# untitled.net
KiCad netlist of a schematic drawn in EAGLE
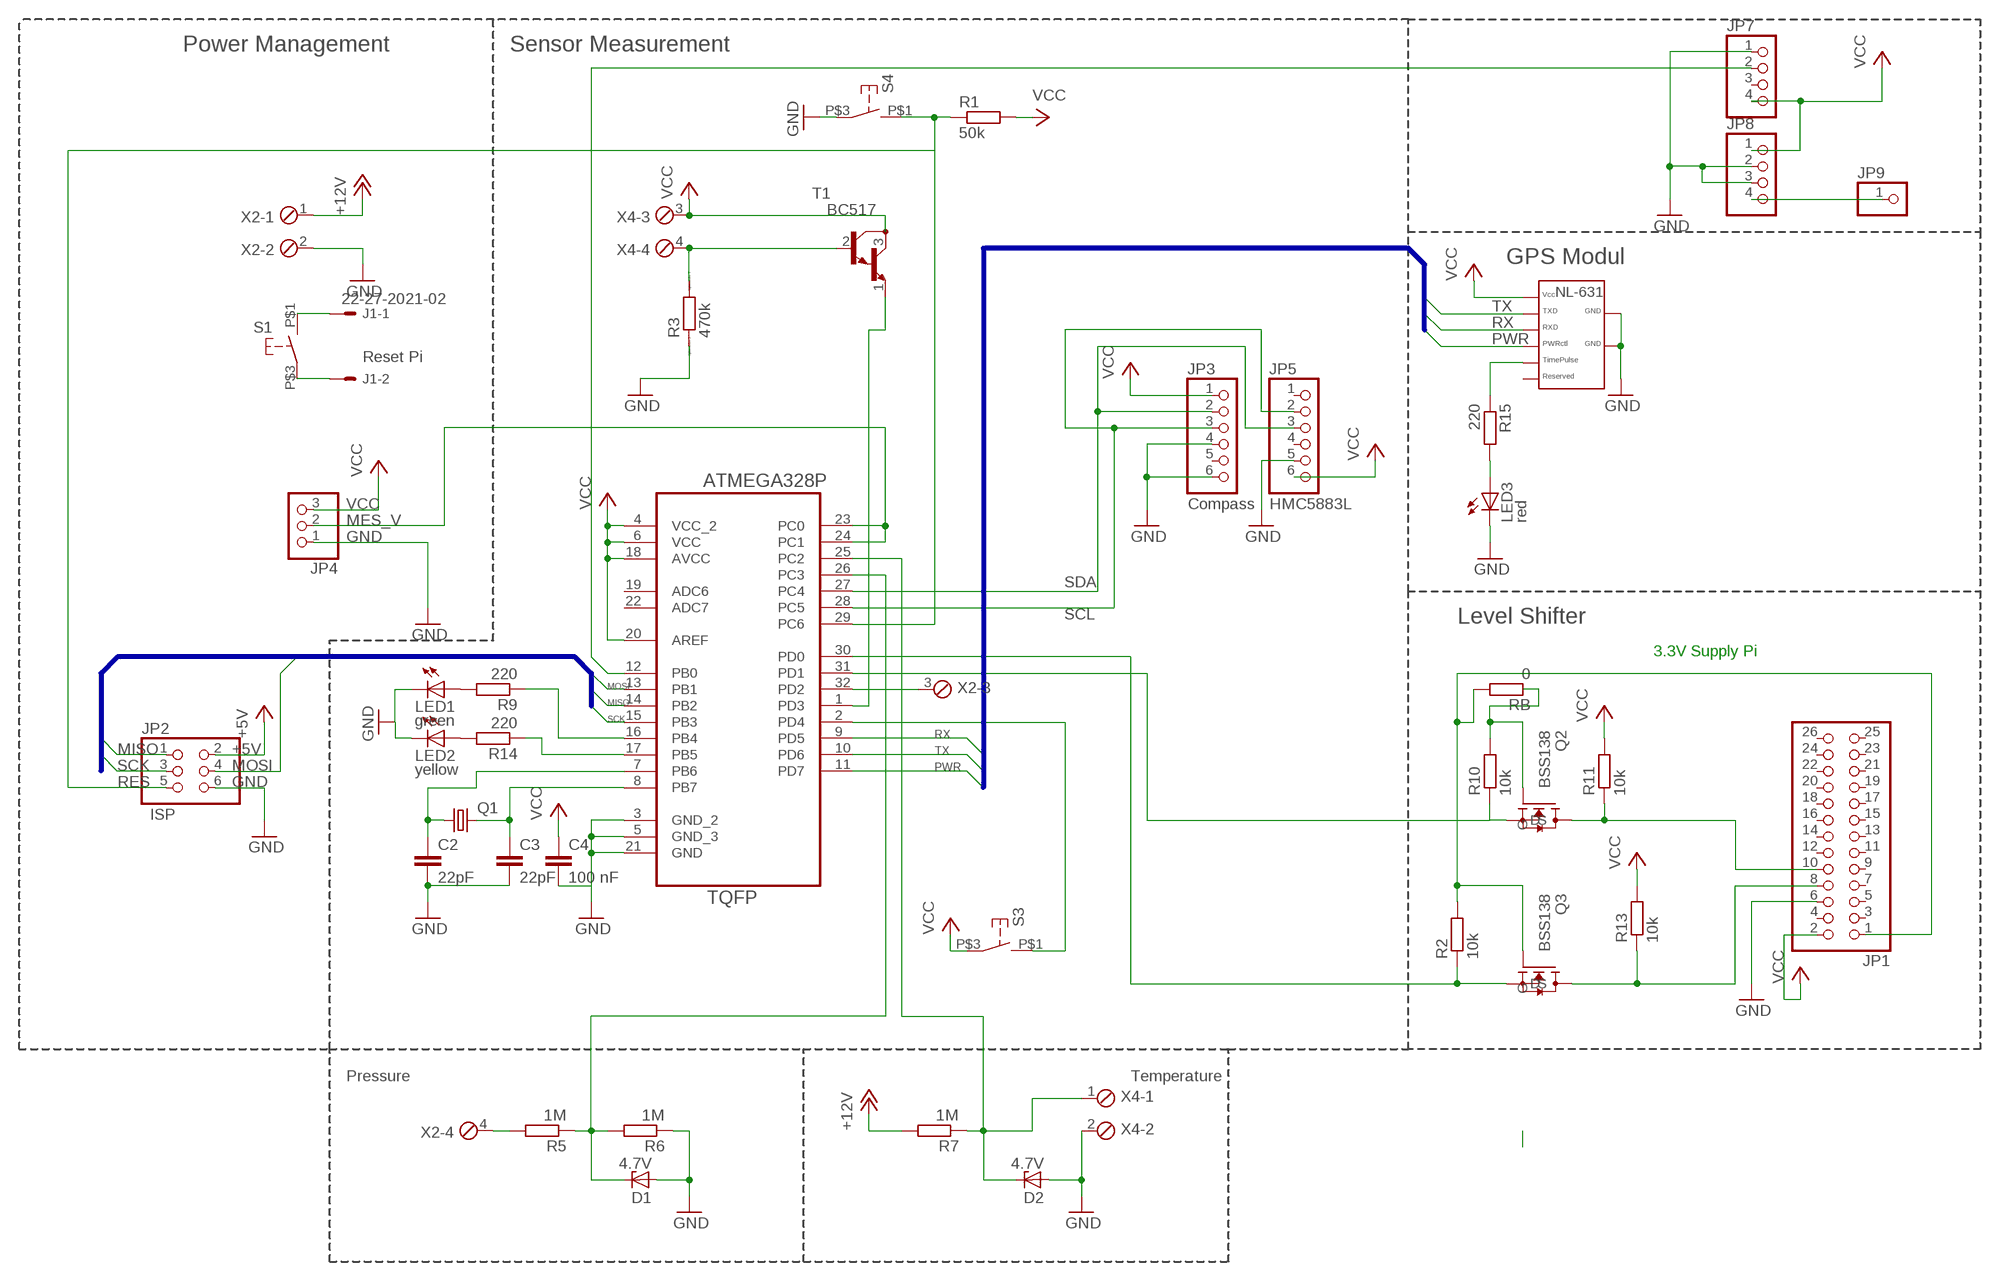
[diagram p0: schematic, sheet 1]

(export (version "E")
  (design (tool "Eeschema 10.0.6"))
  (components
    (comp (ref "C2")
      (value "22pF")
      (footprint "eagle-import:C1206")
      (libsource (lib "eagle-import") (part "C-EUC1206"))
    )
    (comp (ref "C3")
      (value "22pF")
      (footprint "eagle-import:C1206")
      (libsource (lib "eagle-import") (part "C-EUC1206"))
    )
    (comp (ref "C4")
      (value "100 nF")
      (footprint "eagle-import:C0603")
      (libsource (lib "eagle-import") (part "C-EUC0603"))
    )
    (comp (ref "D1")
      (value "4.7V")
      (footprint "eagle-import:SOT23")
      (libsource (lib "eagle-import") (part "ZENER-DIODESOT23"))
    )
    (comp (ref "D2")
      (value "4.7V")
      (footprint "eagle-import:SOT23")
      (libsource (lib "eagle-import") (part "ZENER-DIODESOT23"))
    )
    (comp (ref "IC1")
      (value "ATMEGA328P-AU")
      (footprint "eagle-import:QFP80P900X900X120-32N")
      (libsource (lib "eagle-import") (part "ATMEGA328P-AU"))
    )
    (comp (ref "J1")
      (value "22-27-2021-02")
      (footprint "eagle-import:6410-02")
      (libsource (lib "eagle-import") (part "22-?-0227-2021"))
    )
    (comp (ref "JP1")
      (value "PINHD-2X13")
      (footprint "eagle-import:2X13")
      (libsource (lib "eagle-import") (part "PINHD-2X13"))
    )
    (comp (ref "JP2")
      (value "PINHD-2X3")
      (footprint "eagle-import:2X03")
      (libsource (lib "eagle-import") (part "PINHD-2X3"))
    )
    (comp (ref "JP3")
      (value "Compass")
      (footprint "eagle-import:1X06")
      (libsource (lib "eagle-import") (part "PINHD-1X6"))
    )
    (comp (ref "JP4")
      (value "PINHD-1X3")
      (footprint "eagle-import:1X03")
      (libsource (lib "eagle-import") (part "PINHD-1X3"))
    )
    (comp (ref "JP5")
      (value "HMC5883L")
      (footprint "eagle-import:1X06")
      (libsource (lib "eagle-import") (part "PINHD-1X6"))
    )
    (comp (ref "JP7")
      (value "PINHD-1X4")
      (footprint "eagle-import:1X04")
      (libsource (lib "eagle-import") (part "PINHD-1X4"))
    )
    (comp (ref "JP8")
      (value "PINHD-1X4")
      (footprint "eagle-import:1X04")
      (libsource (lib "eagle-import") (part "PINHD-1X4"))
    )
    (comp (ref "JP9")
      (value "PINHD-1X1")
      (footprint "eagle-import:1X01")
      (libsource (lib "eagle-import") (part "PINHD-1X1"))
    )
    (comp (ref "LED1")
      (value "green")
      (footprint "eagle-import:LED3MM")
      (libsource (lib "eagle-import") (part "LED3MM"))
    )
    (comp (ref "LED2")
      (value "yellow")
      (footprint "eagle-import:LED3MM")
      (libsource (lib "eagle-import") (part "LED3MM"))
    )
    (comp (ref "LED3")
      (value "red")
      (footprint "eagle-import:LED3MM")
      (libsource (lib "eagle-import") (part "LED3MM"))
    )
    (comp (ref "Q1")
      (value "CRYSTALHC49UP")
      (footprint "eagle-import:HC49UP")
      (libsource (lib "eagle-import") (part "CRYSTALHC49UP"))
    )
    (comp (ref "Q2")
      (value "BSS138")
      (footprint "eagle-import:BSS138")
      (libsource (lib "eagle-import") (part "BSS138"))
    )
    (comp (ref "Q3")
      (value "BSS138")
      (footprint "eagle-import:BSS138")
      (libsource (lib "eagle-import") (part "BSS138"))
    )
    (comp (ref "R1")
      (value "50k")
      (footprint "eagle-import:R1206")
      (libsource (lib "eagle-import") (part "resistor_R-EU_R1206"))
    )
    (comp (ref "R2")
      (value "10k")
      (footprint "eagle-import:R1206")
      (libsource (lib "eagle-import") (part "resistor_R-EU_R1206"))
    )
    (comp (ref "R3")
      (value "470k")
      (footprint "eagle-import:R1206")
      (libsource (lib "eagle-import") (part "RR1206"))
    )
    (comp (ref "R5")
      (value "1M")
      (footprint "eagle-import:R1206")
      (libsource (lib "eagle-import") (part "R-EU_R1206"))
    )
    (comp (ref "R6")
      (value "1M")
      (footprint "eagle-import:R1206")
      (libsource (lib "eagle-import") (part "R-EU_R1206"))
    )
    (comp (ref "R7")
      (value "1M")
      (footprint "eagle-import:R1206")
      (libsource (lib "eagle-import") (part "R-EU_R1206"))
    )
    (comp (ref "R9")
      (value "220")
      (footprint "eagle-import:R1206")
      (libsource (lib "eagle-import") (part "resistor_R-EU_R1206"))
    )
    (comp (ref "R10")
      (value "10k")
      (footprint "eagle-import:R1206")
      (libsource (lib "eagle-import") (part "resistor_R-EU_R1206"))
    )
    (comp (ref "R11")
      (value "10k")
      (footprint "eagle-import:R1206")
      (libsource (lib "eagle-import") (part "resistor_R-EU_R1206"))
    )
    (comp (ref "R13")
      (value "10k")
      (footprint "eagle-import:R1206")
      (libsource (lib "eagle-import") (part "resistor_R-EU_R1206"))
    )
    (comp (ref "R14")
      (value "220")
      (footprint "eagle-import:R1206")
      (libsource (lib "eagle-import") (part "resistor_R-EU_R1206"))
    )
    (comp (ref "R15")
      (value "220")
      (footprint "eagle-import:R1206")
      (libsource (lib "eagle-import") (part "resistor_R-EU_R1206"))
    )
    (comp (ref "RB")
      (value "0")
      (footprint "eagle-import:R1206")
      (libsource (lib "eagle-import") (part "resistor_R-EU_R1206"))
    )
    (comp (ref "S1")
      (value "SCHLIESSER_TASTSCHALTER")
      (footprint "eagle-import:NAMAE-JTP-1130")
      (libsource (lib "eagle-import") (part "SCHLIESSER_TASTSCHALTER"))
    )
    (comp (ref "S3")
      (value "SCHLIESSER_TASTSCHALTER")
      (footprint "eagle-import:NAMAE-JTP-1130")
      (libsource (lib "eagle-import") (part "SCHLIESSER_TASTSCHALTER"))
    )
    (comp (ref "S4")
      (value "SCHLIESSER_TASTSCHALTER")
      (footprint "eagle-import:NAMAE-JTP-1130")
      (libsource (lib "eagle-import") (part "SCHLIESSER_TASTSCHALTER"))
    )
    (comp (ref "T1")
      (value "BC517")
      (footprint "eagle-import:TO92")
      (libsource (lib "eagle-import") (part "BC517"))
    )
    (comp (ref "U$2")
      (value "NAVILOK-NL-631ETTL")
      (footprint "eagle-import:NAVILOK-NL-631ETTL")
      (libsource (lib "eagle-import") (part "NAVILOK-NL-631ETTL"))
    )
    (comp (ref "X2")
      (value "MPT4")
      (footprint "eagle-import:4POL254")
      (libsource (lib "eagle-import") (part "MPT4"))
    )
    (comp (ref "X4")
      (value "MPT4")
      (footprint "eagle-import:4POL254")
      (libsource (lib "eagle-import") (part "MPT4"))
    )
  )
  (nets
    (net (code "1") (name "+5V") (class "Default")
      (node (ref "JP2") (pin "2") (pinfunction "2_2") (pintype "passive"))
    )
    (net (code "2") (name "+12V") (class "Default")
      (node (ref "R7") (pin "2") (pinfunction "2_2") (pintype "passive"))
      (node (ref "X2") (pin "1") (pinfunction "1_1") (pintype "passive"))
    )
    (net (code "3") (name "/MES_V") (class "Default")
      (node (ref "IC1") (pin "23") (pinfunction "PC0_23") (pintype "bidirectional"))
      (node (ref "IC1") (pin "24") (pinfunction "PC1_24") (pintype "bidirectional"))
      (node (ref "JP4") (pin "2") (pinfunction "2_2") (pintype "passive"))
    )
    (net (code "4") (name "/MISO") (class "Default")
      (node (ref "IC1") (pin "14") (pinfunction "PB2_14") (pintype "bidirectional"))
      (node (ref "JP2") (pin "1") (pinfunction "1_1") (pintype "passive"))
    )
    (net (code "5") (name "/MOSI") (class "Default")
      (node (ref "IC1") (pin "13") (pinfunction "PB1_13") (pintype "bidirectional"))
      (node (ref "JP2") (pin "4") (pinfunction "4_4") (pintype "passive"))
    )
    (net (code "6") (name "/PWR") (class "Default")
      (node (ref "IC1") (pin "11") (pinfunction "PD7_11") (pintype "bidirectional"))
      (node (ref "U$2") (pin "P$4") (pinfunction "P$4_P$4") (pintype "bidirectional"))
    )
    (net (code "7") (name "/RES") (class "Default")
      (node (ref "IC1") (pin "29") (pinfunction "PC6_29") (pintype "bidirectional"))
      (node (ref "JP2") (pin "5") (pinfunction "5_5") (pintype "passive"))
      (node (ref "R1") (pin "1") (pinfunction "1_1") (pintype "passive"))
      (node (ref "S4") (pin "P$1") (pinfunction "3_P$1") (pintype "input"))
    )
    (net (code "8") (name "/RX") (class "Default")
      (node (ref "IC1") (pin "9") (pinfunction "PD5_9") (pintype "bidirectional"))
      (node (ref "U$2") (pin "P$3") (pinfunction "P$3_P$3") (pintype "bidirectional"))
    )
    (net (code "9") (name "/SCK") (class "Default")
      (node (ref "IC1") (pin "15") (pinfunction "PB3_15") (pintype "bidirectional"))
      (node (ref "JP2") (pin "3") (pinfunction "3_3") (pintype "passive"))
    )
    (net (code "10") (name "/TX") (class "Default")
      (node (ref "IC1") (pin "10") (pinfunction "PD6_10") (pintype "bidirectional"))
      (node (ref "U$2") (pin "P$2") (pinfunction "P$2_P$2") (pintype "bidirectional"))
    )
    (net (code "11") (name "GND") (class "Default")
      (node (ref "C2") (pin "2") (pinfunction "2_2") (pintype "passive"))
      (node (ref "C3") (pin "2") (pinfunction "2_2") (pintype "passive"))
      (node (ref "C4") (pin "2") (pinfunction "2_2") (pintype "passive"))
      (node (ref "D1") (pin "1") (pinfunction "A_1") (pintype "passive"))
      (node (ref "D2") (pin "1") (pinfunction "A_1") (pintype "passive"))
      (node (ref "IC1") (pin "21") (pinfunction "GND_21") (pintype "passive"))
      (node (ref "IC1") (pin "3") (pinfunction "GND_2_3") (pintype "passive"))
      (node (ref "IC1") (pin "5") (pinfunction "GND_3_5") (pintype "passive"))
      (node (ref "JP1") (pin "6") (pinfunction "6_6") (pintype "passive"))
      (node (ref "JP2") (pin "6") (pinfunction "6_6") (pintype "passive"))
      (node (ref "JP3") (pin "4") (pinfunction "4_4") (pintype "passive"))
      (node (ref "JP3") (pin "6") (pinfunction "6_6") (pintype "passive"))
      (node (ref "JP4") (pin "1") (pinfunction "1_1") (pintype "passive"))
      (node (ref "JP5") (pin "5") (pinfunction "5_5") (pintype "passive"))
      (node (ref "JP7") (pin "1") (pinfunction "1_1") (pintype "passive"))
      (node (ref "JP8") (pin "2") (pinfunction "2_2") (pintype "passive"))
      (node (ref "JP8") (pin "3") (pinfunction "3_3") (pintype "passive"))
      (node (ref "LED1") (pin "K") (pinfunction "C_K") (pintype "passive"))
      (node (ref "LED2") (pin "K") (pinfunction "C_K") (pintype "passive"))
      (node (ref "LED3") (pin "K") (pinfunction "C_K") (pintype "passive"))
      (node (ref "R3") (pin "1") (pinfunction "1_1") (pintype "passive"))
      (node (ref "R6") (pin "1") (pinfunction "1_1") (pintype "passive"))
      (node (ref "S4") (pin "P$3") (pinfunction "4_P$3") (pintype "input"))
      (node (ref "U$2") (pin "P$7") (pinfunction "P$7_P$7") (pintype "bidirectional"))
      (node (ref "U$2") (pin "P$8") (pinfunction "P$8_P$8") (pintype "bidirectional"))
      (node (ref "X2") (pin "2") (pinfunction "1_2") (pintype "passive"))
      (node (ref "X4") (pin "2") (pinfunction "1_2") (pintype "passive"))
    )
    (net (code "12") (name "Net-(D1-C)") (class "Default")
      (node (ref "D1") (pin "3") (pinfunction "C_3") (pintype "passive"))
      (node (ref "IC1") (pin "26") (pinfunction "PC3_26") (pintype "bidirectional"))
      (node (ref "R5") (pin "1") (pinfunction "1_1") (pintype "passive"))
      (node (ref "R6") (pin "2") (pinfunction "2_2") (pintype "passive"))
    )
    (net (code "13") (name "Net-(D2-C)") (class "Default")
      (node (ref "D2") (pin "3") (pinfunction "C_3") (pintype "passive"))
      (node (ref "IC1") (pin "25") (pinfunction "PC2_25") (pintype "bidirectional"))
      (node (ref "R7") (pin "1") (pinfunction "1_1") (pintype "passive"))
      (node (ref "X4") (pin "1") (pinfunction "1_1") (pintype "passive"))
    )
    (net (code "14") (name "Net-(IC1-PB0)") (class "Default")
      (node (ref "IC1") (pin "12") (pinfunction "PB0_12") (pintype "bidirectional"))
      (node (ref "JP7") (pin "2") (pinfunction "2_2") (pintype "passive"))
    )
    (net (code "15") (name "Net-(IC1-PB4)") (class "Default")
      (node (ref "IC1") (pin "16") (pinfunction "PB4_16") (pintype "bidirectional"))
      (node (ref "R9") (pin "1") (pinfunction "1_1") (pintype "passive"))
    )
    (net (code "16") (name "Net-(IC1-PB5)") (class "Default")
      (node (ref "IC1") (pin "17") (pinfunction "PB5_17") (pintype "bidirectional"))
      (node (ref "R14") (pin "1") (pinfunction "1_1") (pintype "passive"))
    )
    (net (code "17") (name "Net-(IC1-PB6)") (class "Default")
      (node (ref "C2") (pin "1") (pinfunction "1_1") (pintype "passive"))
      (node (ref "IC1") (pin "7") (pinfunction "PB6_7") (pintype "bidirectional"))
      (node (ref "Q1") (pin "1") (pinfunction "1_1") (pintype "passive"))
    )
    (net (code "18") (name "Net-(IC1-PB7)") (class "Default")
      (node (ref "C3") (pin "1") (pinfunction "1_1") (pintype "passive"))
      (node (ref "IC1") (pin "8") (pinfunction "PB7_8") (pintype "bidirectional"))
      (node (ref "Q1") (pin "2") (pinfunction "2_2") (pintype "passive"))
    )
    (net (code "19") (name "Net-(IC1-PC4)") (class "Default")
      (node (ref "IC1") (pin "27") (pinfunction "PC4_27") (pintype "bidirectional"))
      (node (ref "JP3") (pin "2") (pinfunction "2_2") (pintype "passive"))
      (node (ref "JP5") (pin "3") (pinfunction "3_3") (pintype "passive"))
    )
    (net (code "20") (name "Net-(IC1-PC5)") (class "Default")
      (node (ref "IC1") (pin "28") (pinfunction "PC5_28") (pintype "bidirectional"))
      (node (ref "JP3") (pin "3") (pinfunction "3_3") (pintype "passive"))
      (node (ref "JP5") (pin "2") (pinfunction "2_2") (pintype "passive"))
    )
    (net (code "21") (name "Net-(IC1-PD0)") (class "Default")
      (node (ref "IC1") (pin "30") (pinfunction "PD0_30") (pintype "bidirectional"))
      (node (ref "Q3") (pin "S") (pinfunction "S_S") (pintype "passive"))
      (node (ref "R2") (pin "1") (pinfunction "1_1") (pintype "passive"))
    )
    (net (code "22") (name "Net-(IC1-PD1)") (class "Default")
      (node (ref "IC1") (pin "31") (pinfunction "PD1_31") (pintype "bidirectional"))
      (node (ref "Q2") (pin "S") (pinfunction "S_S") (pintype "passive"))
      (node (ref "R10") (pin "1") (pinfunction "1_1") (pintype "passive"))
    )
    (net (code "23") (name "Net-(IC1-PD2)") (class "Default")
      (node (ref "IC1") (pin "32") (pinfunction "PD2_32") (pintype "bidirectional"))
      (node (ref "X2") (pin "3") (pinfunction "1_3") (pintype "passive"))
    )
    (net (code "24") (name "Net-(IC1-PD3)") (class "Default")
      (node (ref "IC1") (pin "1") (pinfunction "PD3_1") (pintype "bidirectional"))
      (node (ref "T1") (pin "1") (pinfunction "E_1") (pintype "passive"))
    )
    (net (code "25") (name "Net-(IC1-PD4)") (class "Default")
      (node (ref "IC1") (pin "2") (pinfunction "PD4_2") (pintype "bidirectional"))
      (node (ref "S3") (pin "P$1") (pinfunction "3_P$1") (pintype "input"))
    )
    (net (code "26") (name "Net-(J1A-S)") (class "Default")
      (node (ref "J1") (pin "1") (pinfunction "S_1") (pintype "passive"))
      (node (ref "S1") (pin "P$1") (pinfunction "3_P$1") (pintype "input"))
    )
    (net (code "27") (name "Net-(J1B-S)") (class "Default")
      (node (ref "J1") (pin "2") (pinfunction "S_2") (pintype "passive"))
      (node (ref "S1") (pin "P$3") (pinfunction "4_P$3") (pintype "input"))
    )
    (net (code "28") (name "Net-(JP1-Pad1)") (class "Default")
      (node (ref "JP1") (pin "1") (pinfunction "1_1") (pintype "passive"))
      (node (ref "Q3") (pin "G") (pinfunction "G_G") (pintype "passive"))
      (node (ref "R2") (pin "2") (pinfunction "2_2") (pintype "passive"))
      (node (ref "RB") (pin "2") (pinfunction "2_2") (pintype "passive"))
    )
    (net (code "29") (name "Net-(JP1-Pad8)") (class "Default")
      (node (ref "JP1") (pin "8") (pinfunction "8_8") (pintype "passive"))
      (node (ref "Q3") (pin "D") (pinfunction "D_D") (pintype "passive"))
      (node (ref "R13") (pin "1") (pinfunction "1_1") (pintype "passive"))
    )
    (net (code "30") (name "Net-(JP1-Pad10)") (class "Default")
      (node (ref "JP1") (pin "10") (pinfunction "10_10") (pintype "passive"))
      (node (ref "Q2") (pin "D") (pinfunction "D_D") (pintype "passive"))
      (node (ref "R11") (pin "1") (pinfunction "1_1") (pintype "passive"))
    )
    (net (code "31") (name "Net-(JP8-Pad4)") (class "Default")
      (node (ref "JP8") (pin "4") (pinfunction "4_4") (pintype "passive"))
      (node (ref "JP9") (pin "1") (pinfunction "1_1") (pintype "passive"))
    )
    (net (code "32") (name "Net-(LED1-PadA)") (class "Default")
      (node (ref "LED1") (pin "A") (pinfunction "A_A") (pintype "passive"))
      (node (ref "R9") (pin "2") (pinfunction "2_2") (pintype "passive"))
    )
    (net (code "33") (name "Net-(LED2-PadA)") (class "Default")
      (node (ref "LED2") (pin "A") (pinfunction "A_A") (pintype "passive"))
      (node (ref "R14") (pin "2") (pinfunction "2_2") (pintype "passive"))
    )
    (net (code "34") (name "Net-(LED3-PadA)") (class "Default")
      (node (ref "LED3") (pin "A") (pinfunction "A_A") (pintype "passive"))
      (node (ref "R15") (pin "2") (pinfunction "2_2") (pintype "passive"))
    )
    (net (code "35") (name "Net-(Q2-PadG)") (class "Default")
      (node (ref "Q2") (pin "G") (pinfunction "G_G") (pintype "passive"))
      (node (ref "R10") (pin "2") (pinfunction "2_2") (pintype "passive"))
      (node (ref "RB") (pin "1") (pinfunction "1_1") (pintype "passive"))
    )
    (net (code "36") (name "Net-(R15-Pad1)") (class "Default")
      (node (ref "R15") (pin "1") (pinfunction "1_1") (pintype "passive"))
      (node (ref "U$2") (pin "P$5") (pinfunction "P$5_P$5") (pintype "bidirectional"))
    )
    (net (code "37") (name "Net-(T1-B)") (class "Default")
      (node (ref "R3") (pin "2") (pinfunction "2_2") (pintype "passive"))
      (node (ref "T1") (pin "2") (pinfunction "B_2") (pintype "passive"))
      (node (ref "X4") (pin "4") (pinfunction "1_4") (pintype "passive"))
    )
    (net (code "38") (name "Net-(X2D-1)") (class "Default")
      (node (ref "R5") (pin "2") (pinfunction "2_2") (pintype "passive"))
      (node (ref "X2") (pin "4") (pinfunction "1_4") (pintype "passive"))
    )
    (net (code "39") (name "VCC") (class "Default")
      (node (ref "C4") (pin "1") (pinfunction "1_1") (pintype "passive"))
      (node (ref "IC1") (pin "18") (pinfunction "AVCC_18") (pintype "power_in"))
      (node (ref "IC1") (pin "20") (pinfunction "AREF_20") (pintype "input"))
      (node (ref "IC1") (pin "4") (pinfunction "VCC_2_4") (pintype "power_in"))
      (node (ref "IC1") (pin "6") (pinfunction "VCC_6") (pintype "power_in"))
      (node (ref "JP1") (pin "2") (pinfunction "2_2") (pintype "passive"))
      (node (ref "JP3") (pin "1") (pinfunction "1_1") (pintype "passive"))
      (node (ref "JP4") (pin "3") (pinfunction "3_3") (pintype "passive"))
      (node (ref "JP5") (pin "6") (pinfunction "6_6") (pintype "passive"))
      (node (ref "JP7") (pin "4") (pinfunction "4_4") (pintype "passive"))
      (node (ref "JP8") (pin "1") (pinfunction "1_1") (pintype "passive"))
      (node (ref "R1") (pin "2") (pinfunction "2_2") (pintype "passive"))
      (node (ref "R11") (pin "2") (pinfunction "2_2") (pintype "passive"))
      (node (ref "R13") (pin "2") (pinfunction "2_2") (pintype "passive"))
      (node (ref "S3") (pin "P$3") (pinfunction "4_P$3") (pintype "input"))
      (node (ref "T1") (pin "3") (pinfunction "C_3") (pintype "passive"))
      (node (ref "U$2") (pin "P$1") (pinfunction "P$1_P$1") (pintype "bidirectional"))
      (node (ref "X4") (pin "3") (pinfunction "1_3") (pintype "passive"))
    )
    (net (code "40") (name "unconnected-(IC1-ADC6-Pad19)") (class "Default")
      (node (ref "IC1") (pin "19") (pinfunction "ADC6_19") (pintype "input"))
    )
    (net (code "41") (name "unconnected-(IC1-ADC7-Pad22)") (class "Default")
      (node (ref "IC1") (pin "22") (pinfunction "ADC7_22") (pintype "input"))
    )
    (net (code "42") (name "unconnected-(JP1-Pad3)") (class "Default")
      (node (ref "JP1") (pin "3") (pinfunction "3_3") (pintype "passive"))
    )
    (net (code "43") (name "unconnected-(JP1-Pad4)") (class "Default")
      (node (ref "JP1") (pin "4") (pinfunction "4_4") (pintype "passive"))
    )
    (net (code "44") (name "unconnected-(JP1-Pad5)") (class "Default")
      (node (ref "JP1") (pin "5") (pinfunction "5_5") (pintype "passive"))
    )
    (net (code "45") (name "unconnected-(JP1-Pad7)") (class "Default")
      (node (ref "JP1") (pin "7") (pinfunction "7_7") (pintype "passive"))
    )
    (net (code "46") (name "unconnected-(JP1-Pad9)") (class "Default")
      (node (ref "JP1") (pin "9") (pinfunction "9_9") (pintype "passive"))
    )
    (net (code "47") (name "unconnected-(JP1-Pad11)") (class "Default")
      (node (ref "JP1") (pin "11") (pinfunction "11_11") (pintype "passive"))
    )
    (net (code "48") (name "unconnected-(JP1-Pad12)") (class "Default")
      (node (ref "JP1") (pin "12") (pinfunction "12_12") (pintype "passive"))
    )
    (net (code "49") (name "unconnected-(JP1-Pad13)") (class "Default")
      (node (ref "JP1") (pin "13") (pinfunction "13_13") (pintype "passive"))
    )
    (net (code "50") (name "unconnected-(JP1-Pad14)") (class "Default")
      (node (ref "JP1") (pin "14") (pinfunction "14_14") (pintype "passive"))
    )
    (net (code "51") (name "unconnected-(JP1-Pad15)") (class "Default")
      (node (ref "JP1") (pin "15") (pinfunction "15_15") (pintype "passive"))
    )
    (net (code "52") (name "unconnected-(JP1-Pad16)") (class "Default")
      (node (ref "JP1") (pin "16") (pinfunction "16_16") (pintype "passive"))
    )
    (net (code "53") (name "unconnected-(JP1-Pad17)") (class "Default")
      (node (ref "JP1") (pin "17") (pinfunction "17_17") (pintype "passive"))
    )
    (net (code "54") (name "unconnected-(JP1-Pad18)") (class "Default")
      (node (ref "JP1") (pin "18") (pinfunction "18_18") (pintype "passive"))
    )
    (net (code "55") (name "unconnected-(JP1-Pad19)") (class "Default")
      (node (ref "JP1") (pin "19") (pinfunction "19_19") (pintype "passive"))
    )
    (net (code "56") (name "unconnected-(JP1-Pad20)") (class "Default")
      (node (ref "JP1") (pin "20") (pinfunction "20_20") (pintype "passive"))
    )
    (net (code "57") (name "unconnected-(JP1-Pad21)") (class "Default")
      (node (ref "JP1") (pin "21") (pinfunction "21_21") (pintype "passive"))
    )
    (net (code "58") (name "unconnected-(JP1-Pad22)") (class "Default")
      (node (ref "JP1") (pin "22") (pinfunction "22_22") (pintype "passive"))
    )
    (net (code "59") (name "unconnected-(JP1-Pad23)") (class "Default")
      (node (ref "JP1") (pin "23") (pinfunction "23_23") (pintype "passive"))
    )
    (net (code "60") (name "unconnected-(JP1-Pad24)") (class "Default")
      (node (ref "JP1") (pin "24") (pinfunction "24_24") (pintype "passive"))
    )
    (net (code "61") (name "unconnected-(JP1-Pad25)") (class "Default")
      (node (ref "JP1") (pin "25") (pinfunction "25_25") (pintype "passive"))
    )
    (net (code "62") (name "unconnected-(JP1-Pad26)") (class "Default")
      (node (ref "JP1") (pin "26") (pinfunction "26_26") (pintype "passive"))
    )
    (net (code "63") (name "unconnected-(JP3-Pad5)") (class "Default")
      (node (ref "JP3") (pin "5") (pinfunction "5_5") (pintype "passive"))
    )
    (net (code "64") (name "unconnected-(JP5-Pad1)") (class "Default")
      (node (ref "JP5") (pin "1") (pinfunction "1_1") (pintype "passive"))
    )
    (net (code "65") (name "unconnected-(JP5-Pad4)") (class "Default")
      (node (ref "JP5") (pin "4") (pinfunction "4_4") (pintype "passive"))
    )
    (net (code "66") (name "unconnected-(JP7-Pad3)") (class "Default")
      (node (ref "JP7") (pin "3") (pinfunction "3_3") (pintype "passive"))
    )
    (net (code "67") (name "unconnected-(U$2-PadP$6)") (class "Default")
      (node (ref "U$2") (pin "P$6") (pinfunction "P$6_P$6") (pintype "bidirectional"))
    )
  )
)
